# rectifier.net
KiCad netlist of a schematic drawn in EAGLE
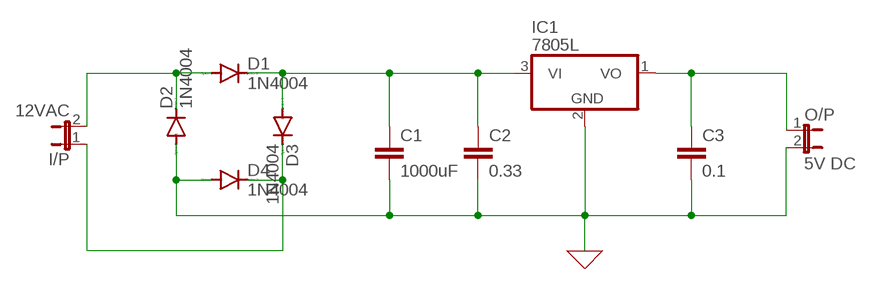
[diagram p0: schematic, sheet 1]

(export (version "E")
  (design (tool "Eeschema 10.0.6"))
  (components
    (comp (ref "C1")
      (value "1000uF")
      (footprint "eagle-import:C2.5-3")
      (libsource (lib "eagle-import") (part "C2,5-3"))
    )
    (comp (ref "C2")
      (value "0.33")
      (footprint "eagle-import:C2.5-3")
      (libsource (lib "eagle-import") (part "C2,5-3"))
    )
    (comp (ref "C3")
      (value "0.1")
      (footprint "eagle-import:C2.5-3")
      (libsource (lib "eagle-import") (part "C2,5-3"))
    )
    (comp (ref "D1")
      (value "1N4004")
      (footprint "eagle-import:DO41-10")
      (libsource (lib "eagle-import") (part "1N4004"))
    )
    (comp (ref "D2")
      (value "1N4004")
      (footprint "eagle-import:DO41-10")
      (libsource (lib "eagle-import") (part "1N4004"))
    )
    (comp (ref "D3")
      (value "1N4004")
      (footprint "eagle-import:DO41-10")
      (libsource (lib "eagle-import") (part "1N4004"))
    )
    (comp (ref "D4")
      (value "1N4004")
      (footprint "eagle-import:DO41-10")
      (libsource (lib "eagle-import") (part "1N4004"))
    )
    (comp (ref "I/P")
      (value "12VAC")
      (footprint "eagle-import:JP1")
      (libsource (lib "eagle-import") (part "JP1E"))
    )
    (comp (ref "IC1")
      (value "7805L")
      (footprint "eagle-import:TO92")
      (libsource (lib "eagle-import") (part "78L05"))
    )
    (comp (ref "O/P")
      (value "5V DC")
      (footprint "eagle-import:JP1")
      (libsource (lib "eagle-import") (part "JP1E"))
    )
  )
  (nets
    (net (code "1") (name "GND") (class "Default")
      (node (ref "C1") (pin "2") (pinfunction "2_2") (pintype "passive"))
      (node (ref "C2") (pin "2") (pinfunction "2_2") (pintype "passive"))
      (node (ref "C3") (pin "2") (pinfunction "2_2") (pintype "passive"))
      (node (ref "D2") (pin "A") (pinfunction "A_A") (pintype "passive"))
      (node (ref "D4") (pin "A") (pinfunction "A_A") (pintype "passive"))
      (node (ref "IC1") (pin "2") (pinfunction "GND_2") (pintype "passive"))
      (node (ref "O/P") (pin "2") (pinfunction "2_2") (pintype "passive"))
    )
    (net (code "2") (name "Net-(D1-PadA)") (class "Default")
      (node (ref "D1") (pin "A") (pinfunction "A_A") (pintype "passive"))
      (node (ref "D2") (pin "C") (pinfunction "C_C") (pintype "passive"))
      (node (ref "I/P") (pin "2") (pinfunction "2_2") (pintype "passive"))
    )
    (net (code "3") (name "Net-(D3-PadC)") (class "Default")
      (node (ref "D3") (pin "C") (pinfunction "C_C") (pintype "passive"))
      (node (ref "D4") (pin "C") (pinfunction "C_C") (pintype "passive"))
      (node (ref "I/P") (pin "1") (pinfunction "1_1") (pintype "passive"))
    )
    (net (code "4") (name "Net-(IC1-VI)") (class "Default")
      (node (ref "C1") (pin "1") (pinfunction "1_1") (pintype "passive"))
      (node (ref "C2") (pin "1") (pinfunction "1_1") (pintype "passive"))
      (node (ref "D1") (pin "C") (pinfunction "C_C") (pintype "passive"))
      (node (ref "D3") (pin "A") (pinfunction "A_A") (pintype "passive"))
      (node (ref "IC1") (pin "3") (pinfunction "VI_3") (pintype "input"))
    )
    (net (code "5") (name "Net-(IC1-VO)") (class "Default")
      (node (ref "C3") (pin "1") (pinfunction "1_1") (pintype "passive"))
      (node (ref "IC1") (pin "1") (pinfunction "VO_1") (pintype "passive"))
      (node (ref "O/P") (pin "1") (pinfunction "1_1") (pintype "passive"))
    )
  )
)
